# amplificadorAudio.net
KiCad netlist of a schematic drawn in Altium Designer
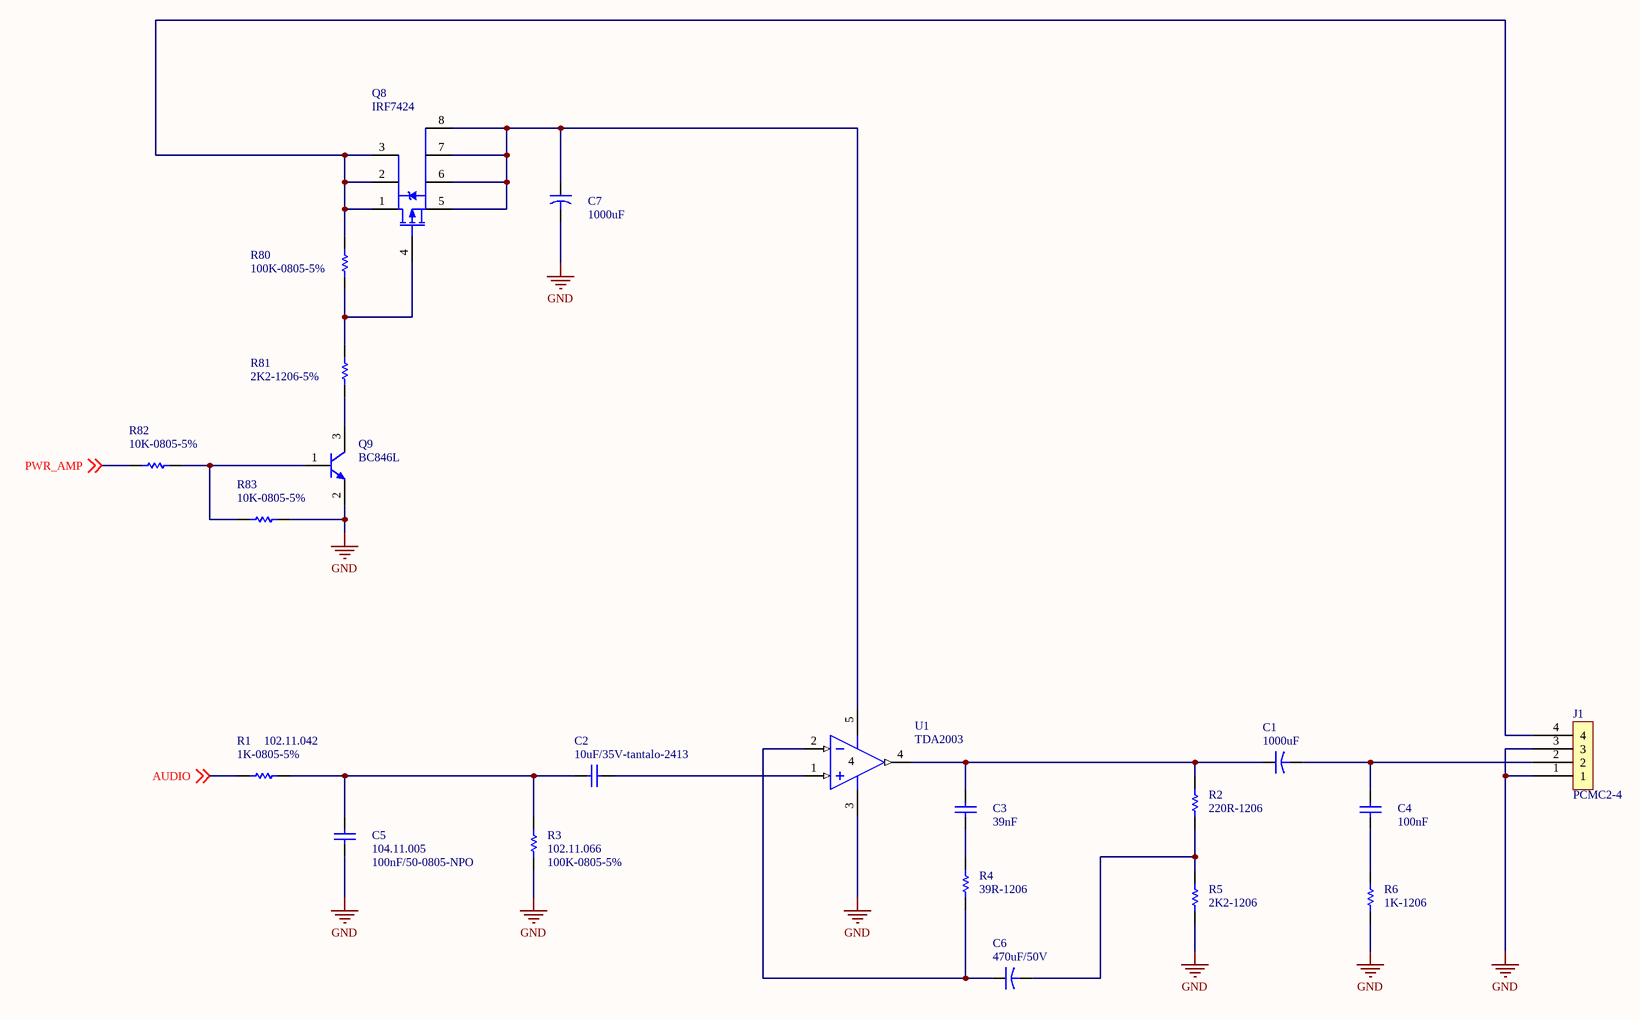
[diagram p0: amplificadorAudio.SchDoc]

(export (version "E")
  (design (tool "Eeschema 10.0.6"))
  (components
    (comp (ref "C1")
      (value "1000uF")
      (footprint "CAP 10X5")
      (description "470uF/50V")
      (libsource (lib "AquinoLib") (part "470uF/50V"))
    )
    (comp (ref "C2")
      (value "10uF/35V-tantalo-2413")
      (footprint "CAP POL 5x11mm")
      (libsource (lib "AquinoLib") (part "10uF/35V-tantalo-2413"))
    )
    (comp (ref "C3")
      (value "39nF")
      (footprint "1206-REVISADO ONDA")
      (description "100nF/50-0805-NPO")
      (libsource (lib "AquinoLib") (part "100nF/50-0805-NPO"))
    )
    (comp (ref "C4")
      (value "100nF")
      (footprint "1206-REVISADO ONDA")
      (description "100nF/50-0805-NPO")
      (libsource (lib "AquinoLib") (part "100nF/50-0805-NPO"))
    )
    (comp (ref "C5")
      (value "100nF/50-0805-NPO")
      (footprint "0805-REVISADO ONDA")
      (fields (field (name "ERP") "104.11.005"))
      (libsource (lib "AquinoLib") (part "100nF/50-0805-NPO"))
    )
    (comp (ref "C6")
      (value "470uF/50V")
      (footprint "CAP 10X5")
      (libsource (lib "AquinoLib") (part "470uF/50V"))
    )
    (comp (ref "C7")
      (value "1000uF")
      (footprint "CAP 10X5")
      (description "470uF/50V")
      (libsource (lib "AquinoLib") (part "470uF/50V"))
    )
    (comp (ref "J1") (value "PCMC2-4") (footprint "PCMC2-4") (libsource (lib "AquinoLib") (part "PCMC2-4")))
    (comp (ref "Q8") (value "IRF7424") (footprint "SOIC-08") (libsource (lib "AquinoLib") (part "IRF7424")))
    (comp (ref "Q9")
      (value "BC846L")
      (footprint "SOT23 - REVISADO ONDA")
      (libsource (lib "AquinoLib") (part "BC846"))
    )
    (comp (ref "R1")
      (value "1K-0805-5%")
      (footprint "0805-REVISADO ONDA")
      (fields (field (name "ERP") "102.11.042"))
      (libsource (lib "AquinoLib") (part "1K-0805-5%"))
    )
    (comp (ref "R2")
      (value "220R-1206")
      (footprint "1206-REVISADO ONDA")
      (description "390R-2512-5%")
      (libsource (lib "AquinoLib") (part "390R-2512-5%"))
    )
    (comp (ref "R3")
      (value "100K-0805-5%")
      (footprint "0805-REVISADO ONDA")
      (fields (field (name "ERP") "102.11.066"))
      (libsource (lib "AquinoLib") (part "100K-0805-5%"))
    )
    (comp (ref "R4")
      (value "39R-1206")
      (footprint "1206-REVISADO ONDA")
      (description "390R-2512-5%")
      (libsource (lib "AquinoLib") (part "390R-2512-5%"))
    )
    (comp (ref "R5")
      (value "2K2-1206")
      (footprint "1206-REVISADO ONDA")
      (description "390R-2512-5%")
      (libsource (lib "AquinoLib") (part "390R-2512-5%"))
    )
    (comp (ref "R6")
      (value "1K-1206")
      (footprint "1206-REVISADO ONDA")
      (description "390R-2512-5%")
      (libsource (lib "AquinoLib") (part "390R-2512-5%"))
    )
    (comp (ref "R80")
      (value "100K-0805-5%")
      (footprint "0805-REVISADO ONDA")
      (libsource (lib "AquinoLib") (part "100K-0805-5%"))
    )
    (comp (ref "R81")
      (value "2K2-1206-5%")
      (footprint "1206-REVISADO ONDA")
      (libsource (lib "AquinoLib") (part "2K2-1206-5%"))
    )
    (comp (ref "R82")
      (value "10K-0805-5%")
      (footprint "0805-REVISADO ONDA")
      (libsource (lib "AquinoLib") (part "10K-0805-5%"))
    )
    (comp (ref "R83")
      (value "10K-0805-5%")
      (footprint "0805-REVISADO ONDA")
      (libsource (lib "AquinoLib") (part "10K-0805-5%"))
    )
    (comp (ref "U1")
      (value "TDA2003")
      (footprint "PENTAWATT V")
      (libsource (lib "AquinoLib") (part "TDA2003"))
    )
  )
  (nets
    (net (code "1") (name "AUDIO") (class "Default")
      (node (ref "R1") (pin "1") (pinfunction "1_1") (pintype "passive"))
    )
    (net (code "2") (name "GND") (class "Default")
      (node (ref "C5") (pin "1") (pinfunction "1_1") (pintype "passive"))
      (node (ref "C7") (pin "2") (pinfunction "2_2") (pintype "passive"))
      (node (ref "J1") (pin "1") (pinfunction "1_1") (pintype "passive"))
      (node (ref "J1") (pin "3") (pinfunction "3_3") (pintype "passive"))
      (node (ref "Q9") (pin "2") (pinfunction "E_2") (pintype "passive"))
      (node (ref "R3") (pin "1") (pinfunction "1_1") (pintype "passive"))
      (node (ref "R5") (pin "2") (pinfunction "2_2") (pintype "passive"))
      (node (ref "R6") (pin "2") (pinfunction "2_2") (pintype "passive"))
      (node (ref "R83") (pin "2") (pinfunction "2_2") (pintype "passive"))
      (node (ref "U1") (pin "3") (pinfunction "GND_3") (pintype "power_in"))
    )
    (net (code "3") (name "Net-(C1-Pad2)") (class "Default")
      (node (ref "C1") (pin "2") (pinfunction "2_2") (pintype "passive"))
      (node (ref "C4") (pin "2") (pinfunction "2_2") (pintype "passive"))
      (node (ref "J1") (pin "2") (pinfunction "2_2") (pintype "passive"))
    )
    (net (code "4") (name "Net-(C2-Pad1)") (class "Default")
      (node (ref "C2") (pin "1") (pinfunction "1_1") (pintype "passive"))
      (node (ref "C5") (pin "2") (pinfunction "2_2") (pintype "passive"))
      (node (ref "R1") (pin "2") (pinfunction "2_2") (pintype "passive"))
      (node (ref "R3") (pin "2") (pinfunction "2_2") (pintype "passive"))
    )
    (net (code "5") (name "Net-(C3-Pad1)") (class "Default")
      (node (ref "C3") (pin "1") (pinfunction "1_1") (pintype "passive"))
      (node (ref "R4") (pin "1") (pinfunction "1_1") (pintype "passive"))
    )
    (net (code "6") (name "Net-(C4-Pad1)") (class "Default")
      (node (ref "C4") (pin "1") (pinfunction "1_1") (pintype "passive"))
      (node (ref "R6") (pin "1") (pinfunction "1_1") (pintype "passive"))
    )
    (net (code "7") (name "Net-(C6-Pad2)") (class "Default")
      (node (ref "C6") (pin "2") (pinfunction "2_2") (pintype "passive"))
      (node (ref "R2") (pin "2") (pinfunction "2_2") (pintype "passive"))
      (node (ref "R5") (pin "1") (pinfunction "1_1") (pintype "passive"))
    )
    (net (code "8") (name "Net-(J1-Pad4)") (class "Default")
      (node (ref "J1") (pin "4") (pinfunction "4_4") (pintype "passive"))
      (node (ref "Q8") (pin "1") (pinfunction "S2_1") (pintype "passive"))
      (node (ref "Q8") (pin "2") (pinfunction "S2_2") (pintype "passive"))
      (node (ref "Q8") (pin "3") (pinfunction "S2_3") (pintype "passive"))
      (node (ref "R80") (pin "2") (pinfunction "2_2") (pintype "passive"))
    )
    (net (code "9") (name "Net-(Q8-G2)") (class "Default")
      (node (ref "Q8") (pin "4") (pinfunction "G2_4") (pintype "passive"))
      (node (ref "R80") (pin "1") (pinfunction "1_1") (pintype "passive"))
      (node (ref "R81") (pin "2") (pinfunction "2_2") (pintype "passive"))
    )
    (net (code "10") (name "Net-(Q9-B)") (class "Default")
      (node (ref "Q9") (pin "1") (pinfunction "B_1") (pintype "passive"))
      (node (ref "R82") (pin "2") (pinfunction "2_2") (pintype "passive"))
      (node (ref "R83") (pin "1") (pinfunction "1_1") (pintype "passive"))
    )
    (net (code "11") (name "Net-(Q9-C)") (class "Default")
      (node (ref "Q9") (pin "3") (pinfunction "C_3") (pintype "passive"))
      (node (ref "R81") (pin "1") (pinfunction "1_1") (pintype "passive"))
    )
    (net (code "12") (name "Net-(U1-IN+)") (class "Default")
      (node (ref "C2") (pin "2") (pinfunction "2_2") (pintype "passive"))
      (node (ref "U1") (pin "1") (pinfunction "IN+_1") (pintype "input"))
    )
    (net (code "13") (name "Net-(U1-IN-)") (class "Default")
      (node (ref "C6") (pin "1") (pinfunction "1_1") (pintype "passive"))
      (node (ref "R4") (pin "2") (pinfunction "2_2") (pintype "passive"))
      (node (ref "U1") (pin "2") (pinfunction "IN-_2") (pintype "input"))
    )
    (net (code "14") (name "Net-(U1-OUT)") (class "Default")
      (node (ref "C1") (pin "1") (pinfunction "1_1") (pintype "passive"))
      (node (ref "C3") (pin "2") (pinfunction "2_2") (pintype "passive"))
      (node (ref "R2") (pin "1") (pinfunction "1_1") (pintype "passive"))
      (node (ref "U1") (pin "4") (pinfunction "OUT_4") (pintype "output"))
    )
    (net (code "15") (name "Net-(U1-V+)") (class "Default")
      (node (ref "C7") (pin "1") (pinfunction "1_1") (pintype "passive"))
      (node (ref "Q8") (pin "5") (pinfunction "D2_5") (pintype "passive"))
      (node (ref "Q8") (pin "6") (pinfunction "D2_6") (pintype "passive"))
      (node (ref "Q8") (pin "7") (pinfunction "D2_7") (pintype "passive"))
      (node (ref "Q8") (pin "8") (pinfunction "D2_8") (pintype "passive"))
      (node (ref "U1") (pin "5") (pinfunction "V+_5") (pintype "power_in"))
    )
    (net (code "16") (name "PWR_AMP") (class "Default")
      (node (ref "R82") (pin "1") (pinfunction "1_1") (pintype "passive"))
    )
  )
)
